# USB_Interface.net
KiCad netlist of a schematic drawn in Altium Designer
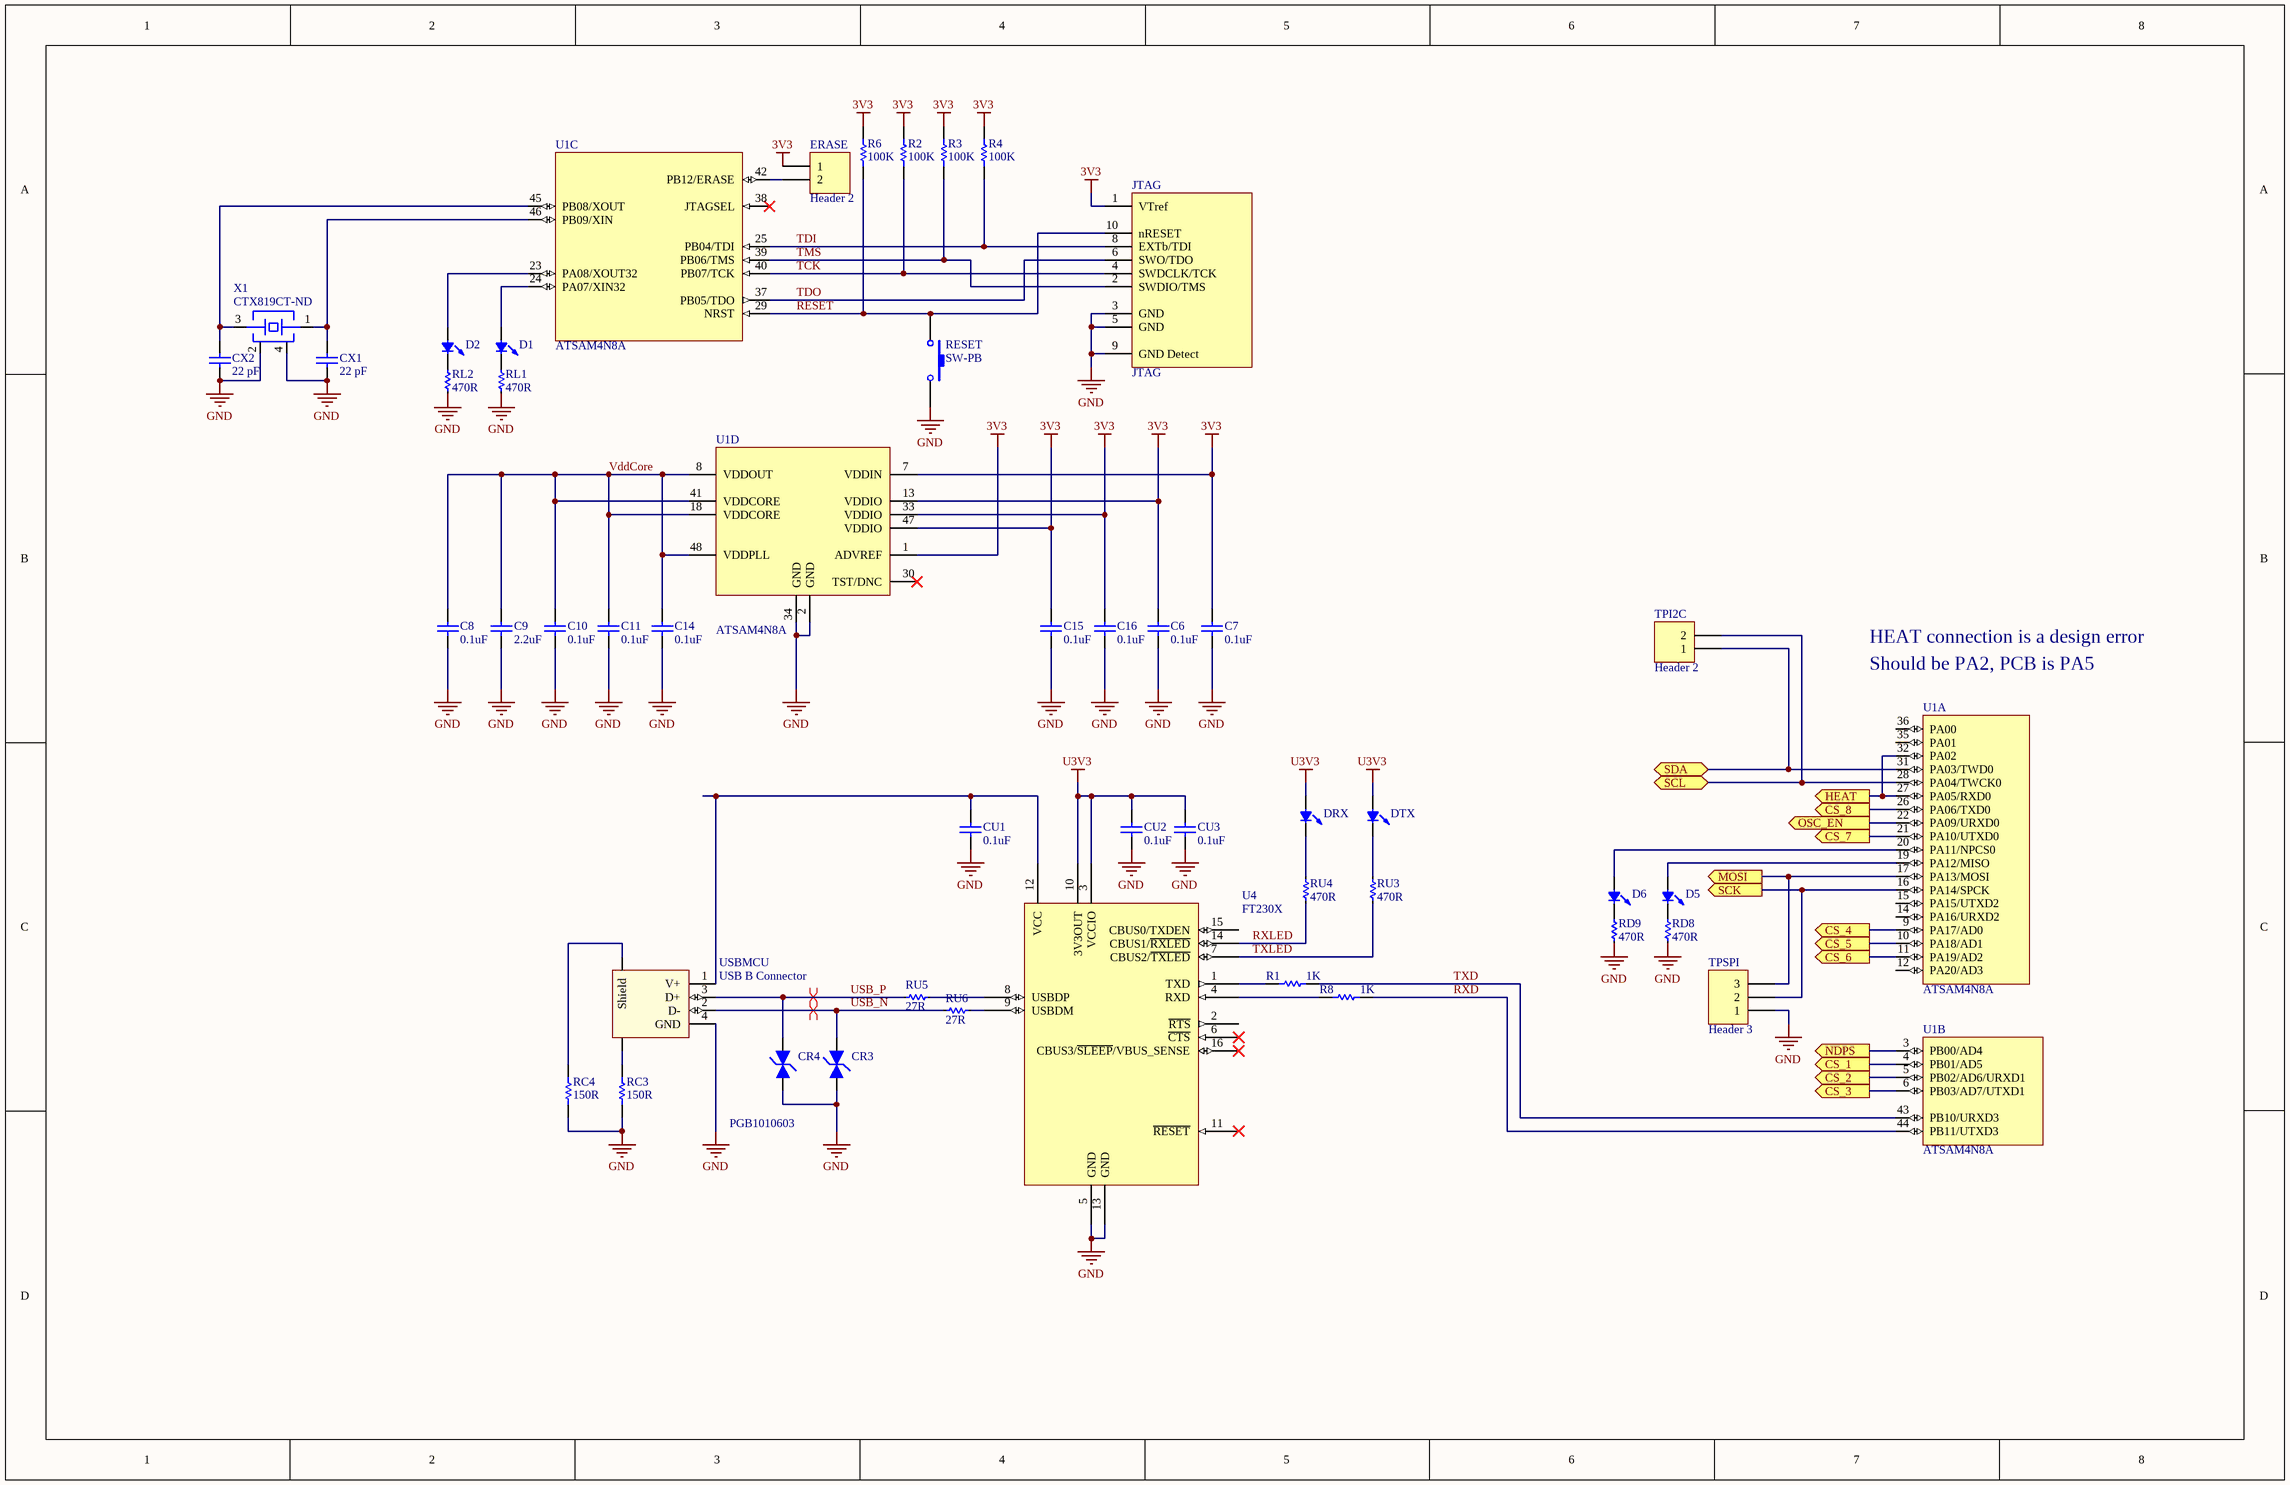
[diagram p0: USB Interface.SchDoc]

(export (version "E")
  (design (tool "Eeschema 10.0.6"))
  (components
    (comp (ref "C6")
      (value "0.1uF")
      (footprint "0603C")
      (description "Capacitor (Semiconductor SIM Model)")
      (fields (field (name "Comment") "Cap Semi") (field (name "PUBLISHER") "Altium Limited"))
      (libsource (lib "Miscellaneous Devices") (part "Cap Semi"))
    )
    (comp (ref "C7")
      (value "0.1uF")
      (footprint "0603C")
      (description "Capacitor (Semiconductor SIM Model)")
      (fields (field (name "Comment") "Cap Semi") (field (name "PUBLISHER") "Altium Limited"))
      (libsource (lib "Miscellaneous Devices") (part "Cap Semi"))
    )
    (comp (ref "C8")
      (value "0.1uF")
      (footprint "0603C")
      (description "Capacitor (Semiconductor SIM Model)")
      (fields (field (name "Comment") "Cap Semi") (field (name "PUBLISHER") "Altium Limited"))
      (libsource (lib "Miscellaneous Devices") (part "Cap Semi"))
    )
    (comp (ref "C9")
      (value "2.2uF")
      (footprint "1206C")
      (description "Capacitor (Semiconductor SIM Model)")
      (fields (field (name "Comment") "Cap Semi") (field (name "PUBLISHER") "Altium Limited"))
      (libsource (lib "Miscellaneous Devices") (part "Cap Semi"))
    )
    (comp (ref "C10")
      (value "0.1uF")
      (footprint "0603C")
      (description "Capacitor (Semiconductor SIM Model)")
      (fields (field (name "Comment") "Cap Semi") (field (name "PUBLISHER") "Altium Limited"))
      (libsource (lib "Miscellaneous Devices") (part "Cap Semi"))
    )
    (comp (ref "C11")
      (value "0.1uF")
      (footprint "0603C")
      (description "Capacitor (Semiconductor SIM Model)")
      (fields (field (name "Comment") "Cap Semi") (field (name "PUBLISHER") "Altium Limited"))
      (libsource (lib "Miscellaneous Devices") (part "Cap Semi"))
    )
    (comp (ref "C14")
      (value "0.1uF")
      (footprint "0603C")
      (description "Capacitor (Semiconductor SIM Model)")
      (fields (field (name "Comment") "Cap Semi") (field (name "PUBLISHER") "Altium Limited"))
      (libsource (lib "Miscellaneous Devices") (part "Cap Semi"))
    )
    (comp (ref "C15")
      (value "0.1uF")
      (footprint "0603C")
      (description "Capacitor (Semiconductor SIM Model)")
      (fields (field (name "Comment") "Cap Semi") (field (name "PUBLISHER") "Altium Limited"))
      (libsource (lib "Miscellaneous Devices") (part "Cap Semi"))
    )
    (comp (ref "C16")
      (value "0.1uF")
      (footprint "0603C")
      (description "Capacitor (Semiconductor SIM Model)")
      (fields (field (name "Comment") "Cap Semi") (field (name "PUBLISHER") "Altium Limited"))
      (libsource (lib "Miscellaneous Devices") (part "Cap Semi"))
    )
    (comp (ref "CR3")
      (value "PGB1010603")
      (footprint "0603PG")
      (description "PulseGuard® Lead-Free 0603 Surface Mount Polymeric ESD Suppressors")
      (libsource (lib "DAQ System") (part "PGB1010603"))
    )
    (comp (ref "CR4")
      (value "PGB1010603")
      (footprint "0603PG")
      (description "PulseGuard® Lead-Free 0603 Surface Mount Polymeric ESD Suppressors")
      (libsource (lib "DAQ System") (part "PGB1010603"))
    )
    (comp (ref "CU1")
      (value "0.1uF")
      (footprint "0603C")
      (description "Capacitor (Semiconductor SIM Model)")
      (fields (field (name "Comment") "Cap Semi") (field (name "PUBLISHER") "Altium Limited"))
      (libsource (lib "Miscellaneous Devices") (part "Cap Semi"))
    )
    (comp (ref "CU2")
      (value "0.1uF")
      (footprint "0603C")
      (description "Capacitor (Semiconductor SIM Model)")
      (fields (field (name "Comment") "Cap Semi") (field (name "PUBLISHER") "Altium Limited"))
      (libsource (lib "Miscellaneous Devices") (part "Cap Semi"))
    )
    (comp (ref "CU3")
      (value "0.1uF")
      (footprint "0603C")
      (description "Capacitor (Semiconductor SIM Model)")
      (fields (field (name "Comment") "Cap Semi") (field (name "PUBLISHER") "Altium Limited"))
      (libsource (lib "Miscellaneous Devices") (part "Cap Semi"))
    )
    (comp (ref "CX1")
      (value "22 pF")
      (footprint "0603C")
      (description "Capacitor (Semiconductor SIM Model)")
      (fields (field (name "Comment") "Cap Semi") (field (name "PUBLISHER") "Altium Limited"))
      (libsource (lib "Miscellaneous Devices") (part "Cap Semi"))
    )
    (comp (ref "CX2")
      (value "22 pF")
      (footprint "0603C")
      (description "Capacitor (Semiconductor SIM Model)")
      (fields (field (name "Comment") "Cap Semi") (field (name "PUBLISHER") "Altium Limited"))
      (libsource (lib "Miscellaneous Devices") (part "Cap Semi"))
    )
    (comp (ref "D1")
      (value "LED0")
      (footprint "0603 SMT LED")
      (description "T 1 3/4 LED")
      (fields (field (name "PUBLISHER") "Altium Limited"))
      (libsource (lib "Miscellaneous Devices") (part "LED0"))
    )
    (comp (ref "D2")
      (value "LED0")
      (footprint "0603 SMT LED")
      (description "T 1 3/4 LED")
      (fields (field (name "PUBLISHER") "Altium Limited"))
      (libsource (lib "Miscellaneous Devices") (part "LED0"))
    )
    (comp (ref "D5")
      (value "LED0")
      (footprint "0603 SMT LED")
      (description "T 1 3/4 LED")
      (fields (field (name "PUBLISHER") "Altium Limited"))
      (libsource (lib "Miscellaneous Devices") (part "LED0"))
    )
    (comp (ref "D6")
      (value "LED0")
      (footprint "0603 SMT LED")
      (description "T 1 3/4 LED")
      (fields (field (name "PUBLISHER") "Altium Limited"))
      (libsource (lib "Miscellaneous Devices") (part "LED0"))
    )
    (comp (ref "DRX")
      (value "LED0")
      (footprint "0603 SMT LED")
      (description "T 1 3/4 LED")
      (fields (field (name "PUBLISHER") "Altium Limited"))
      (libsource (lib "Miscellaneous Devices") (part "LED0"))
    )
    (comp (ref "DTX")
      (value "LED0")
      (footprint "0603 SMT LED")
      (description "T 1 3/4 LED")
      (fields (field (name "PUBLISHER") "Altium Limited"))
      (libsource (lib "Miscellaneous Devices") (part "LED0"))
    )
    (comp (ref "ERASE")
      (value "Header 2")
      (footprint "HDR1X2")
      (description "Header, 2-Pin")
      (fields (field (name "PUBLISHER") "Altium Limited"))
      (libsource (lib "") (part "Header 2_1"))
    )
    (comp (ref "JTAG")
      (value "JTAG")
      (footprint "MHDR2X5 - Shrouded")
      (description "ARM 10-Pin JTAG Interface")
      (libsource (lib "Connectors") (part "ARM JTAG-10"))
    )
    (comp (ref "R1")
      (value "1K")
      (footprint "0603R")
      (description "Semiconductor Resistor")
      (fields (field (name "Comment") "Res Semi") (field (name "PUBLISHER") "Altium Limited"))
      (libsource (lib "Miscellaneous Devices") (part "Res Semi"))
    )
    (comp (ref "R2")
      (value "100K")
      (footprint "0603R")
      (description "Semiconductor Resistor")
      (fields (field (name "Comment") "Res Semi") (field (name "PUBLISHER") "Altium Limited"))
      (libsource (lib "Miscellaneous Devices") (part "Res Semi"))
    )
    (comp (ref "R3")
      (value "100K")
      (footprint "0603R")
      (description "Semiconductor Resistor")
      (fields (field (name "Comment") "Res Semi") (field (name "PUBLISHER") "Altium Limited"))
      (libsource (lib "Miscellaneous Devices") (part "Res Semi"))
    )
    (comp (ref "R4")
      (value "100K")
      (footprint "0603R")
      (description "Semiconductor Resistor")
      (fields (field (name "Comment") "Res Semi") (field (name "PUBLISHER") "Altium Limited"))
      (libsource (lib "Miscellaneous Devices") (part "Res Semi"))
    )
    (comp (ref "R6")
      (value "100K")
      (footprint "0603R")
      (description "Semiconductor Resistor")
      (fields (field (name "Comment") "Res Semi") (field (name "PUBLISHER") "Altium Limited"))
      (libsource (lib "Miscellaneous Devices") (part "Res Semi"))
    )
    (comp (ref "R8")
      (value "1K")
      (footprint "0603R")
      (description "Semiconductor Resistor")
      (fields (field (name "Comment") "Res Semi") (field (name "PUBLISHER") "Altium Limited"))
      (libsource (lib "Miscellaneous Devices") (part "Res Semi"))
    )
    (comp (ref "RC3")
      (value "150R")
      (footprint "1206R")
      (description "Semiconductor Resistor")
      (fields (field (name "Comment") "Res Semi") (field (name "PUBLISHER") "Altium Limited"))
      (libsource (lib "Miscellaneous Devices") (part "Res Semi"))
    )
    (comp (ref "RC4")
      (value "150R")
      (footprint "1206R")
      (description "Semiconductor Resistor")
      (fields (field (name "Comment") "Res Semi") (field (name "PUBLISHER") "Altium Limited"))
      (libsource (lib "Miscellaneous Devices") (part "Res Semi"))
    )
    (comp (ref "RD8")
      (value "470R")
      (footprint "0603R")
      (description "Semiconductor Resistor")
      (fields (field (name "Comment") "Res Semi Small") (field (name "PUBLISHER") "Altium Limited"))
      (libsource (lib "Miscellaneous Devices") (part "Res Semi Small"))
    )
    (comp (ref "RD9")
      (value "470R")
      (footprint "0603R")
      (description "Semiconductor Resistor")
      (fields (field (name "Comment") "Res Semi Small") (field (name "PUBLISHER") "Altium Limited"))
      (libsource (lib "Miscellaneous Devices") (part "Res Semi Small"))
    )
    (comp (ref "RESET")
      (value "SW-PB")
      (footprint "TL3302BF180QG/TR")
      (description "Switch")
      (fields (field (name "PUBLISHER") "Altium Limited"))
      (libsource (lib "Miscellaneous Devices") (part "SW-PB"))
    )
    (comp (ref "RL1")
      (value "470R")
      (footprint "0603R")
      (description "Semiconductor Resistor")
      (fields (field (name "Comment") "Res Semi Small") (field (name "PUBLISHER") "Altium Limited"))
      (libsource (lib "Miscellaneous Devices") (part "Res Semi Small"))
    )
    (comp (ref "RL2")
      (value "470R")
      (footprint "0603R")
      (description "Semiconductor Resistor")
      (fields (field (name "Comment") "Res Semi Small") (field (name "PUBLISHER") "Altium Limited"))
      (libsource (lib "Miscellaneous Devices") (part "Res Semi Small"))
    )
    (comp (ref "RU3")
      (value "470R")
      (footprint "0603R")
      (description "Semiconductor Resistor")
      (fields (field (name "Comment") "Res Semi Small") (field (name "PUBLISHER") "Altium Limited"))
      (libsource (lib "Miscellaneous Devices") (part "Res Semi Small"))
    )
    (comp (ref "RU4")
      (value "470R")
      (footprint "0603R")
      (description "Semiconductor Resistor")
      (fields (field (name "Comment") "Res Semi Small") (field (name "PUBLISHER") "Altium Limited"))
      (libsource (lib "Miscellaneous Devices") (part "Res Semi Small"))
    )
    (comp (ref "RU5")
      (value "27R")
      (footprint "0603R")
      (description "Semiconductor Resistor")
      (fields (field (name "Comment") "Res Semi Small") (field (name "PUBLISHER") "Altium Limited"))
      (libsource (lib "Miscellaneous Devices") (part "Res Semi Small"))
    )
    (comp (ref "RU6")
      (value "27R")
      (footprint "0603R")
      (description "Semiconductor Resistor")
      (fields (field (name "Comment") "Res Semi Small") (field (name "PUBLISHER") "Altium Limited"))
      (libsource (lib "Miscellaneous Devices") (part "Res Semi Small"))
    )
    (comp (ref "TPI2C")
      (value "Header 2")
      (footprint "HDR1X2")
      (description "Header, 2-Pin")
      (fields (field (name "PUBLISHER") "Altium Limited"))
      (libsource (lib "Miscellaneous Connectors") (part "Header 2"))
    )
    (comp (ref "TPSPI")
      (value "Header 3")
      (footprint "HDR1X3")
      (description "Header, 3-Pin")
      (fields (field (name "PUBLISHER") "Altium Limited"))
      (libsource (lib "Miscellaneous Connectors") (part "Header 3"))
    )
    (comp (ref "U1")
      (value "ATSAM4N8A")
      (footprint "TSQFP50P900X900-48N")
      (description "SAM4N ARM Cortex-M4 Microcontrollers")
      (libsource (lib "") (part "ATSAM4N8A_2"))
    )
    (comp (ref "U4")
      (value "FT230X")
      (footprint "SOP635P600-16AN")
      (description "USB To Basic Serial Bridge IC")
      (libsource (lib "ICs") (part "FT230X"))
    )
    (comp (ref "USBMCU")
      (value "USB B Connector")
      (footprint "USB Connector (type B)")
      (libsource (lib "DAQ Sstem") (part "USB B connector - Through hole"))
    )
    (comp (ref "X1")
      (value "CTX819CT-ND")
      (footprint "Abracon ABM3B Crystal")
      (description "16 MHz Micro SMT Crystal")
      (libsource (lib "Unsorted") (part "SMT Crystal"))
    )
  )
  (nets
    (net (code "1") (name "/CS_1") (class "Default")
      (node (ref "U1") (pin "4") (pinfunction "PB01/AD5_4") (pintype "bidirectional"))
    )
    (net (code "2") (name "/CS_2") (class "Default")
      (node (ref "U1") (pin "5") (pinfunction "PB02/AD6/URXD1_5") (pintype "bidirectional"))
    )
    (net (code "3") (name "/CS_3") (class "Default")
      (node (ref "U1") (pin "6") (pinfunction "PB03/AD7/UTXD1_6") (pintype "bidirectional"))
    )
    (net (code "4") (name "/CS_4") (class "Default")
      (node (ref "U1") (pin "9") (pinfunction "PA17/AD0_9") (pintype "bidirectional"))
    )
    (net (code "5") (name "/CS_5") (class "Default")
      (node (ref "U1") (pin "10") (pinfunction "PA18/AD1_10") (pintype "bidirectional"))
    )
    (net (code "6") (name "/CS_6") (class "Default")
      (node (ref "U1") (pin "11") (pinfunction "PA19/AD2_11") (pintype "bidirectional"))
    )
    (net (code "7") (name "/CS_7") (class "Default")
      (node (ref "U1") (pin "21") (pinfunction "PA10/UTXD0_21") (pintype "bidirectional"))
    )
    (net (code "8") (name "/CS_8") (class "Default")
      (node (ref "U1") (pin "26") (pinfunction "PA06/TXD0_26") (pintype "bidirectional"))
    )
    (net (code "9") (name "/HEAT") (class "Default")
      (node (ref "U1") (pin "27") (pinfunction "PA05/RXD0_27") (pintype "bidirectional"))
      (node (ref "U1") (pin "32") (pinfunction "PA02_32") (pintype "bidirectional"))
    )
    (net (code "10") (name "/MOSI") (class "Default")
      (node (ref "TPSPI") (pin "3") (pinfunction "3_3") (pintype "passive"))
      (node (ref "U1") (pin "17") (pinfunction "PA13/MOSI_17") (pintype "bidirectional"))
    )
    (net (code "11") (name "/NDPS") (class "Default")
      (node (ref "U1") (pin "3") (pinfunction "PB00/AD4_3") (pintype "bidirectional"))
    )
    (net (code "12") (name "/OSC_EN") (class "Default")
      (node (ref "U1") (pin "22") (pinfunction "PA09/URXD0_22") (pintype "bidirectional"))
    )
    (net (code "13") (name "/RESET") (class "Default")
      (node (ref "JTAG") (pin "10") (pinfunction "nRESET_10") (pintype "passive"))
      (node (ref "R6") (pin "1") (pinfunction "1_1") (pintype "passive"))
      (node (ref "RESET") (pin "1") (pinfunction "1_1") (pintype "passive"))
      (node (ref "U1") (pin "29") (pinfunction "NRST_29") (pintype "input"))
    )
    (net (code "14") (name "/RXD") (class "Default")
      (node (ref "R8") (pin "2") (pinfunction "2_2") (pintype "passive"))
      (node (ref "U1") (pin "44") (pinfunction "PB11/UTXD3_44") (pintype "bidirectional"))
    )
    (net (code "15") (name "/RXLED") (class "Default")
      (node (ref "RU4") (pin "2") (pinfunction "2_2") (pintype "passive"))
      (node (ref "U4") (pin "14") (pinfunction "CBUS1/~{RXLED}_14") (pintype "bidirectional"))
    )
    (net (code "16") (name "/SCK") (class "Default")
      (node (ref "TPSPI") (pin "2") (pinfunction "2_2") (pintype "passive"))
      (node (ref "U1") (pin "16") (pinfunction "PA14/SPCK_16") (pintype "bidirectional"))
    )
    (net (code "17") (name "/SCL") (class "Default")
      (node (ref "TPI2C") (pin "2") (pinfunction "2_2") (pintype "passive"))
      (node (ref "U1") (pin "28") (pinfunction "PA04/TWCK0_28") (pintype "bidirectional"))
    )
    (net (code "18") (name "/SDA") (class "Default")
      (node (ref "TPI2C") (pin "1") (pinfunction "1_1") (pintype "passive"))
      (node (ref "U1") (pin "31") (pinfunction "PA03/TWD0_31") (pintype "bidirectional"))
    )
    (net (code "19") (name "/TCK") (class "Default")
      (node (ref "JTAG") (pin "4") (pinfunction "SWDCLK/TCK_4") (pintype "passive"))
      (node (ref "R2") (pin "1") (pinfunction "1_1") (pintype "passive"))
      (node (ref "U1") (pin "40") (pinfunction "PB07/TCK_40") (pintype "input"))
    )
    (net (code "20") (name "/TDI") (class "Default")
      (node (ref "JTAG") (pin "8") (pinfunction "EXTb/TDI_8") (pintype "passive"))
      (node (ref "R4") (pin "1") (pinfunction "1_1") (pintype "passive"))
      (node (ref "U1") (pin "25") (pinfunction "PB04/TDI_25") (pintype "input"))
    )
    (net (code "21") (name "/TDO") (class "Default")
      (node (ref "JTAG") (pin "6") (pinfunction "SWO/TDO_6") (pintype "passive"))
      (node (ref "U1") (pin "37") (pinfunction "PB05/TDO_37") (pintype "output"))
    )
    (net (code "22") (name "/TMS") (class "Default")
      (node (ref "JTAG") (pin "2") (pinfunction "SWDIO/TMS_2") (pintype "passive"))
      (node (ref "R3") (pin "1") (pinfunction "1_1") (pintype "passive"))
      (node (ref "U1") (pin "39") (pinfunction "PB06/TMS_39") (pintype "input"))
    )
    (net (code "23") (name "/TXD") (class "Default")
      (node (ref "R1") (pin "2") (pinfunction "2_2") (pintype "passive"))
      (node (ref "U1") (pin "43") (pinfunction "PB10/URXD3_43") (pintype "bidirectional"))
    )
    (net (code "24") (name "/TXLED") (class "Default")
      (node (ref "RU3") (pin "2") (pinfunction "2_2") (pintype "passive"))
      (node (ref "U4") (pin "7") (pinfunction "CBUS2/~{TXLED}_7") (pintype "bidirectional"))
    )
    (net (code "25") (name "/USB_N") (class "Default")
      (node (ref "CR3") (pin "1") (pinfunction "1_1") (pintype "passive"))
      (node (ref "RU6") (pin "1") (pinfunction "1_1") (pintype "passive"))
      (node (ref "USBMCU") (pin "2") (pinfunction "D-_2") (pintype "bidirectional"))
    )
    (net (code "26") (name "/USB_P") (class "Default")
      (node (ref "CR4") (pin "1") (pinfunction "1_1") (pintype "passive"))
      (node (ref "RU5") (pin "1") (pinfunction "1_1") (pintype "passive"))
      (node (ref "USBMCU") (pin "3") (pinfunction "D+_3") (pintype "bidirectional"))
    )
    (net (code "27") (name "/VddCore") (class "Default")
      (node (ref "C10") (pin "2") (pinfunction "2_2") (pintype "passive"))
      (node (ref "C11") (pin "2") (pinfunction "2_2") (pintype "passive"))
      (node (ref "C14") (pin "2") (pinfunction "2_2") (pintype "passive"))
      (node (ref "C8") (pin "2") (pinfunction "2_2") (pintype "passive"))
      (node (ref "C9") (pin "2") (pinfunction "2_2") (pintype "passive"))
      (node (ref "U1") (pin "18") (pinfunction "VDDCORE_18") (pintype "power_in"))
      (node (ref "U1") (pin "41") (pinfunction "VDDCORE_41") (pintype "power_in"))
      (node (ref "U1") (pin "48") (pinfunction "VDDPLL_48") (pintype "power_in"))
      (node (ref "U1") (pin "8") (pinfunction "VDDOUT_8") (pintype "power_in"))
    )
    (net (code "28") (name "3V3") (class "Default")
      (node (ref "C15") (pin "2") (pinfunction "2_2") (pintype "passive"))
      (node (ref "C16") (pin "2") (pinfunction "2_2") (pintype "passive"))
      (node (ref "C6") (pin "2") (pinfunction "2_2") (pintype "passive"))
      (node (ref "C7") (pin "2") (pinfunction "2_2") (pintype "passive"))
      (node (ref "ERASE") (pin "1") (pinfunction "1_1") (pintype "passive"))
      (node (ref "JTAG") (pin "1") (pinfunction "VTref_1") (pintype "passive"))
      (node (ref "R2") (pin "2") (pinfunction "2_2") (pintype "passive"))
      (node (ref "R3") (pin "2") (pinfunction "2_2") (pintype "passive"))
      (node (ref "R4") (pin "2") (pinfunction "2_2") (pintype "passive"))
      (node (ref "R6") (pin "2") (pinfunction "2_2") (pintype "passive"))
      (node (ref "U1") (pin "1") (pinfunction "ADVREF_1") (pintype "power_in"))
      (node (ref "U1") (pin "13") (pinfunction "VDDIO_13") (pintype "power_in"))
      (node (ref "U1") (pin "33") (pinfunction "VDDIO_33") (pintype "power_in"))
      (node (ref "U1") (pin "47") (pinfunction "VDDIO_47") (pintype "power_in"))
      (node (ref "U1") (pin "7") (pinfunction "VDDIN_7") (pintype "power_in"))
    )
    (net (code "29") (name "GND") (class "Default")
      (node (ref "C10") (pin "1") (pinfunction "1_1") (pintype "passive"))
      (node (ref "C11") (pin "1") (pinfunction "1_1") (pintype "passive"))
      (node (ref "C14") (pin "1") (pinfunction "1_1") (pintype "passive"))
      (node (ref "C15") (pin "1") (pinfunction "1_1") (pintype "passive"))
      (node (ref "C16") (pin "1") (pinfunction "1_1") (pintype "passive"))
      (node (ref "C6") (pin "1") (pinfunction "1_1") (pintype "passive"))
      (node (ref "C7") (pin "1") (pinfunction "1_1") (pintype "passive"))
      (node (ref "C8") (pin "1") (pinfunction "1_1") (pintype "passive"))
      (node (ref "C9") (pin "1") (pinfunction "1_1") (pintype "passive"))
      (node (ref "CR3") (pin "2") (pinfunction "2_2") (pintype "passive"))
      (node (ref "CR4") (pin "2") (pinfunction "2_2") (pintype "passive"))
      (node (ref "CU1") (pin "1") (pinfunction "1_1") (pintype "passive"))
      (node (ref "CU2") (pin "1") (pinfunction "1_1") (pintype "passive"))
      (node (ref "CU3") (pin "1") (pinfunction "1_1") (pintype "passive"))
      (node (ref "CX1") (pin "1") (pinfunction "1_1") (pintype "passive"))
      (node (ref "CX2") (pin "1") (pinfunction "1_1") (pintype "passive"))
      (node (ref "JTAG") (pin "3") (pinfunction "GND_3") (pintype "power_in"))
      (node (ref "JTAG") (pin "5") (pinfunction "GND_5") (pintype "power_in"))
      (node (ref "JTAG") (pin "9") (pinfunction "GND_Detect_9") (pintype "passive"))
      (node (ref "RC3") (pin "1") (pinfunction "1_1") (pintype "passive"))
      (node (ref "RC4") (pin "1") (pinfunction "1_1") (pintype "passive"))
      (node (ref "RD8") (pin "2") (pinfunction "2_2") (pintype "passive"))
      (node (ref "RD9") (pin "2") (pinfunction "2_2") (pintype "passive"))
      (node (ref "RESET") (pin "2") (pinfunction "2_2") (pintype "passive"))
      (node (ref "RL1") (pin "2") (pinfunction "2_2") (pintype "passive"))
      (node (ref "RL2") (pin "2") (pinfunction "2_2") (pintype "passive"))
      (node (ref "TPSPI") (pin "1") (pinfunction "1_1") (pintype "passive"))
      (node (ref "U1") (pin "2") (pinfunction "GND_2") (pintype "power_in"))
      (node (ref "U1") (pin "34") (pinfunction "GND_34") (pintype "power_in"))
      (node (ref "U4") (pin "13") (pinfunction "GND_13") (pintype "power_in"))
      (node (ref "U4") (pin "5") (pinfunction "GND_5") (pintype "power_in"))
      (node (ref "USBMCU") (pin "4") (pinfunction "GND_4") (pintype "power_in"))
      (node (ref "X1") (pin "2") (pinfunction "2_2") (pintype "passive"))
      (node (ref "X1") (pin "4") (pinfunction "4_4") (pintype "passive"))
    )
    (net (code "30") (name "Net-(D1-Pad2)") (class "Default")
      (node (ref "D1") (pin "2") (pinfunction "2_2") (pintype "passive"))
      (node (ref "RL1") (pin "1") (pinfunction "1_1") (pintype "passive"))
    )
    (net (code "31") (name "Net-(D2-Pad2)") (class "Default")
      (node (ref "D2") (pin "2") (pinfunction "2_2") (pintype "passive"))
      (node (ref "RL2") (pin "1") (pinfunction "1_1") (pintype "passive"))
    )
    (net (code "32") (name "Net-(D5-Pad2)") (class "Default")
      (node (ref "D5") (pin "2") (pinfunction "2_2") (pintype "passive"))
      (node (ref "RD8") (pin "1") (pinfunction "1_1") (pintype "passive"))
    )
    (net (code "33") (name "Net-(D6-Pad2)") (class "Default")
      (node (ref "D6") (pin "2") (pinfunction "2_2") (pintype "passive"))
      (node (ref "RD9") (pin "1") (pinfunction "1_1") (pintype "passive"))
    )
    (net (code "34") (name "Net-(DRX-Pad2)") (class "Default")
      (node (ref "DRX") (pin "2") (pinfunction "2_2") (pintype "passive"))
      (node (ref "RU4") (pin "1") (pinfunction "1_1") (pintype "passive"))
    )
    (net (code "35") (name "Net-(DTX-Pad2)") (class "Default")
      (node (ref "DTX") (pin "2") (pinfunction "2_2") (pintype "passive"))
      (node (ref "RU3") (pin "1") (pinfunction "1_1") (pintype "passive"))
    )
    (net (code "36") (name "Net-(U1A-PA11{slash}NPCS0)") (class "Default")
      (node (ref "D6") (pin "1") (pinfunction "1_1") (pintype "passive"))
      (node (ref "U1") (pin "20") (pinfunction "PA11/NPCS0_20") (pintype "bidirectional"))
    )
    (net (code "37") (name "Net-(U1A-PA12{slash}MISO)") (class "Default")
      (node (ref "D5") (pin "1") (pinfunction "1_1") (pintype "passive"))
      (node (ref "U1") (pin "19") (pinfunction "PA12/MISO_19") (pintype "bidirectional"))
    )
    (net (code "38") (name "Net-(U1C-PA07{slash}XIN32)") (class "Default")
      (node (ref "D1") (pin "1") (pinfunction "1_1") (pintype "passive"))
      (node (ref "U1") (pin "24") (pinfunction "PA07/XIN32_24") (pintype "bidirectional"))
    )
    (net (code "39") (name "Net-(U1C-PA08{slash}XOUT32)") (class "Default")
      (node (ref "D2") (pin "1") (pinfunction "1_1") (pintype "passive"))
      (node (ref "U1") (pin "23") (pinfunction "PA08/XOUT32_23") (pintype "bidirectional"))
    )
    (net (code "40") (name "Net-(U1C-PB08{slash}XOUT)") (class "Default")
      (node (ref "CX2") (pin "2") (pinfunction "2_2") (pintype "passive"))
      (node (ref "U1") (pin "45") (pinfunction "PB08/XOUT_45") (pintype "bidirectional"))
      (node (ref "X1") (pin "3") (pinfunction "3_3") (pintype "passive"))
    )
    (net (code "41") (name "Net-(U1C-PB09{slash}XIN)") (class "Default")
      (node (ref "CX1") (pin "2") (pinfunction "2_2") (pintype "passive"))
      (node (ref "U1") (pin "46") (pinfunction "PB09/XIN_46") (pintype "bidirectional"))
      (node (ref "X1") (pin "1") (pinfunction "1_1") (pintype "passive"))
    )
    (net (code "42") (name "Net-(U1C-PB12{slash}ERASE)") (class "Default")
      (node (ref "ERASE") (pin "2") (pinfunction "2_2") (pintype "passive"))
      (node (ref "U1") (pin "42") (pinfunction "PB12/ERASE_42") (pintype "bidirectional"))
    )
    (net (code "43") (name "Net-(U4-RXD)") (class "Default")
      (node (ref "R8") (pin "1") (pinfunction "1_1") (pintype "passive"))
      (node (ref "U4") (pin "4") (pinfunction "RXD_4") (pintype "input"))
    )
    (net (code "44") (name "Net-(U4-TXD)") (class "Default")
      (node (ref "R1") (pin "1") (pinfunction "1_1") (pintype "passive"))
      (node (ref "U4") (pin "1") (pinfunction "TXD_1") (pintype "output"))
    )
    (net (code "45") (name "Net-(U4-USBDM)") (class "Default")
      (node (ref "RU6") (pin "2") (pinfunction "2_2") (pintype "passive"))
      (node (ref "U4") (pin "9") (pinfunction "USBDM_9") (pintype "bidirectional"))
    )
    (net (code "46") (name "Net-(U4-USBDP)") (class "Default")
      (node (ref "RU5") (pin "2") (pinfunction "2_2") (pintype "passive"))
      (node (ref "U4") (pin "8") (pinfunction "USBDP_8") (pintype "bidirectional"))
    )
    (net (code "47") (name "Net-(U4-VCC)") (class "Default")
      (node (ref "CU1") (pin "2") (pinfunction "2_2") (pintype "passive"))
      (node (ref "U4") (pin "12") (pinfunction "VCC_12") (pintype "power_in"))
      (node (ref "USBMCU") (pin "1") (pinfunction "V+_1") (pintype "power_in"))
    )
    (net (code "48") (name "Net-(USBMCU-Gnd)") (class "Default")
      (node (ref "RC3") (pin "2") (pinfunction "2_2") (pintype "passive"))
      (node (ref "USBMCU") (pin "5") (pinfunction "Gnd_5") (pintype "passive"))
    )
    (net (code "49") (name "Net-(USBMCU-Shield)") (class "Default")
      (node (ref "RC4") (pin "2") (pinfunction "2_2") (pintype "passive"))
      (node (ref "USBMCU") (pin "6") (pinfunction "Shield_6") (pintype "passive"))
    )
    (net (code "50") (name "U3V3") (class "Default")
      (node (ref "CU2") (pin "2") (pinfunction "2_2") (pintype "passive"))
      (node (ref "CU3") (pin "2") (pinfunction "2_2") (pintype "passive"))
      (node (ref "DRX") (pin "1") (pinfunction "1_1") (pintype "passive"))
      (node (ref "DTX") (pin "1") (pinfunction "1_1") (pintype "passive"))
      (node (ref "U4") (pin "10") (pinfunction "3V3OUT_10") (pintype "power_in"))
      (node (ref "U4") (pin "3") (pinfunction "VCCIO_3") (pintype "power_in"))
    )
    (net (code "51") (name "unconnected-(U1A-PA00-Pad36)") (class "Default")
      (node (ref "U1") (pin "36") (pinfunction "PA00_36") (pintype "bidirectional"))
    )
    (net (code "52") (name "unconnected-(U1A-PA01-Pad35)") (class "Default")
      (node (ref "U1") (pin "35") (pinfunction "PA01_35") (pintype "bidirectional"))
    )
    (net (code "53") (name "unconnected-(U1A-PA15{slash}UTXD2-Pad15)") (class "Default")
      (node (ref "U1") (pin "15") (pinfunction "PA15/UTXD2_15") (pintype "bidirectional"))
    )
    (net (code "54") (name "unconnected-(U1A-PA16{slash}URXD2-Pad14)") (class "Default")
      (node (ref "U1") (pin "14") (pinfunction "PA16/URXD2_14") (pintype "bidirectional"))
    )
    (net (code "55") (name "unconnected-(U1A-PA20{slash}AD3-Pad12)") (class "Default")
      (node (ref "U1") (pin "12") (pinfunction "PA20/AD3_12") (pintype "bidirectional"))
    )
    (net (code "56") (name "unconnected-(U1C-JTAGSEL-Pad38)") (class "Default")
      (node (ref "U1") (pin "38") (pinfunction "JTAGSEL_38") (pintype "input+no_connect"))
    )
    (net (code "57") (name "unconnected-(U1D-TST{slash}DNC-Pad30)") (class "Default")
      (node (ref "U1") (pin "30") (pinfunction "TST/DNC_30") (pintype "passive+no_connect"))
    )
    (net (code "58") (name "unconnected-(U4-CBUS0{slash}TXDEN-Pad15)") (class "Default")
      (node (ref "U4") (pin "15") (pinfunction "CBUS0/TXDEN_15") (pintype "bidirectional"))
    )
    (net (code "59") (name "unconnected-(U4-CBUS3{slash}~{SLEEP}{slash}VBUS_SENSE-Pad16)") (class "Default")
      (node (ref "U4") (pin "16") (pinfunction "CBUS3/~{SLEEP}/VBUS_SENSE_16") (pintype "bidirectional+no_connect"))
    )
    (net (code "60") (name "unconnected-(U4-CTS-Pad6)") (class "Default")
      (node (ref "U4") (pin "6") (pinfunction "CTS_6") (pintype "input+no_connect"))
    )
    (net (code "61") (name "unconnected-(U4-NC-Pad8)") (class "Default")
      (node (ref "U4") (pin "8") (pinfunction "NC_8") (pintype "passive"))
    )
    (net (code "62") (name "unconnected-(U4-NC-Pad24)") (class "Default")
      (node (ref "U4") (pin "24") (pinfunction "NC_24") (pintype "passive"))
    )
    (net (code "63") (name "unconnected-(U4-RTS-Pad2)") (class "Default")
      (node (ref "U4") (pin "2") (pinfunction "RTS_2") (pintype "output"))
    )
    (net (code "64") (name "unconnected-(U4-~{RESET}-Pad11)") (class "Default")
      (node (ref "U4") (pin "11") (pinfunction "~{RESET}_11") (pintype "input+no_connect"))
    )
  )
)
